# Current_sensor.net
KiCad netlist of a schematic drawn in Altium Designer
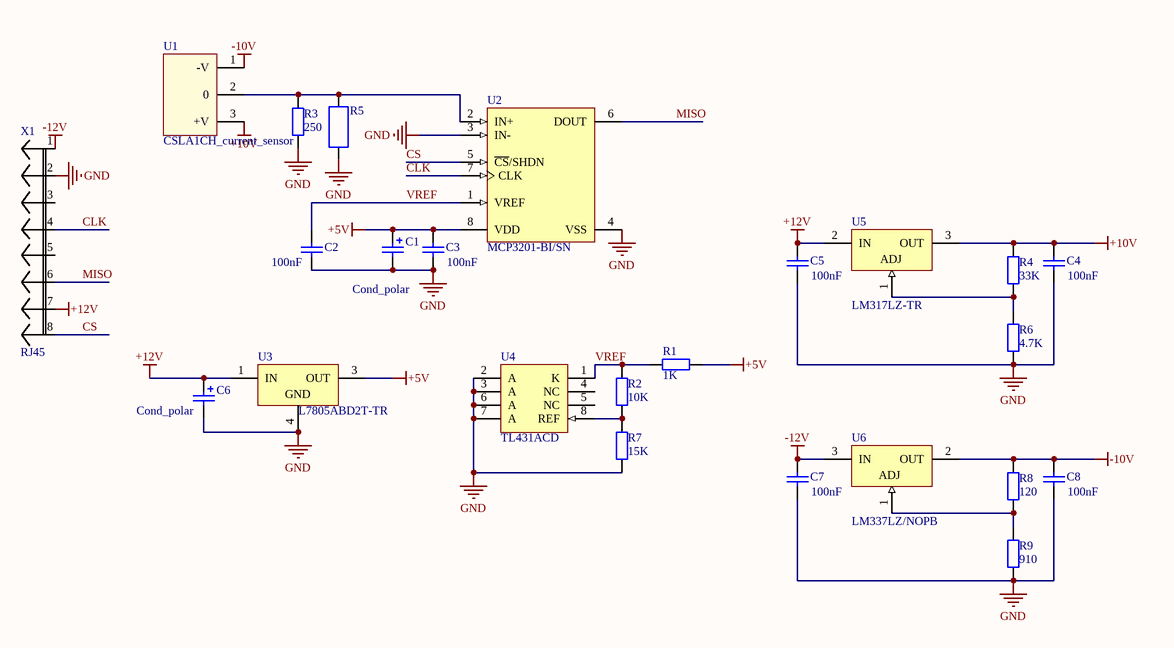
[diagram p0: Current_sensor.SchDoc]

(export (version "E")
  (design (tool "Eeschema 10.0.6"))
  (components
    (comp (ref "C1")
      (value "Cond_polar")
      (footprint "A_H_pcb_lib:CAP_EL_SMD_6.3mm")
      (libsource (lib "A_H_sch_lib") (part "Cond_polar"))
    )
    (comp (ref "C2")
      (value "100nF")
      (footprint "A_H_pcb_lib:C0805")
      (libsource (lib "A_H_sch_lib") (part "Condensator"))
    )
    (comp (ref "C3")
      (value "100nF")
      (footprint "A_H_pcb_lib:C0805")
      (libsource (lib "A_H_sch_lib") (part "Condensator"))
    )
    (comp (ref "C4")
      (value "100nF")
      (footprint "A_H_pcb_lib:C0805")
      (libsource (lib "A_H_sch_lib") (part "Condensator"))
    )
    (comp (ref "C5")
      (value "100nF")
      (footprint "A_H_pcb_lib:C0805")
      (libsource (lib "A_H_sch_lib") (part "Condensator"))
    )
    (comp (ref "C6")
      (value "Cond_polar")
      (footprint "A_H_pcb_lib:CAP_EL_SMD_6.3mm")
      (libsource (lib "A_H_sch_lib") (part "Cond_polar"))
    )
    (comp (ref "C7")
      (value "100nF")
      (footprint "A_H_pcb_lib:C0805")
      (libsource (lib "A_H_sch_lib") (part "Condensator"))
    )
    (comp (ref "C8")
      (value "100nF")
      (footprint "A_H_pcb_lib:C0805")
      (libsource (lib "A_H_sch_lib") (part "Condensator"))
    )
    (comp (ref "R1") (value "1K") (footprint "R0805") (libsource (lib "") (part "Resistor_1")))
    (comp (ref "R2") (value "10K") (footprint "R0805") (libsource (lib "A_H_sch_lib") (part "Resistor")))
    (comp (ref "R3") (value "250") (footprint "R0805") (libsource (lib "") (part "Resistor_2")))
    (comp (ref "R4") (value "33K") (footprint "R0805") (libsource (lib "") (part "Resistor_2")))
    (comp (ref "R5")
      (value "Resirtor_vivodnoi")
      (footprint "res_vivod")
      (libsource (lib "A_H_sch_lib") (part "Resirtor_vivodnoi"))
    )
    (comp (ref "R6") (value "4.7K") (footprint "R0805") (libsource (lib "") (part "Resistor_2")))
    (comp (ref "R7") (value "15K") (footprint "R0805") (libsource (lib "A_H_sch_lib") (part "Resistor")))
    (comp (ref "R8") (value "120") (footprint "R0805") (libsource (lib "") (part "Resistor_2")))
    (comp (ref "R9") (value "910") (footprint "R0805") (libsource (lib "") (part "Resistor_2")))
    (comp (ref "U1")
      (value "CSLA1CH_current_sensor")
      (footprint "A_H_pcb_lib:CSLA1CH_current_sensor")
      (libsource (lib "A_H_sch_lib") (part "CSLA1CH_current_sensor"))
    )
    (comp (ref "U2")
      (value "MCP3201-BI/SN")
      (footprint "SO8")
      (libsource (lib "A_H_sch_lib") (part "MCP3201-BI/SN"))
    )
    (comp (ref "U3")
      (value "L7805ABD2T-TR")
      (footprint "TO-263_N")
      (description "Positive Voltage Regulator, 3-Pin D2PAK, Tape and Reel")
      (libsource (lib "STMicroelectronics Power Management Linear Regulator") (part "L7805ABD2T-TR"))
    )
    (comp (ref "U4")
      (value "TL431ACD")
      (footprint "SO8_N")
      (description "Programmable Voltage Reference")
      (fields (field (name "PUBLISHER") "Altium Limited"))
      (libsource (lib "ST Power Mgt Voltage Reference") (part "TL431ACD"))
    )
    (comp (ref "U5")
      (value "LM317LZ-TR")
      (footprint "TO-92")
      (description "Low Current 1.2 to 37V Adjustable Voltage Regulator, 3-Pin TO-92, Tape and Reel")
      (libsource (lib "STMicroelectronics Power Management Linear Regulator") (part "LM317LZ-TR"))
    )
    (comp (ref "U6")
      (value "LM337LZ/NOPB")
      (footprint "Z03A")
      (description "3-Terminal Adjustable Regulator, 3-pin TO-92, Pb-Free")
      (fields (field (name "MANUFACTURER") "National Semiconductor"))
      (libsource (lib "National Semiconductor LDO") (part "LM337LZ/NOPB"))
    )
    (comp (ref "X1")
      (value "RJ45")
      (footprint "A_H_pcb_lib:RJ45")
      (libsource (lib "A_H_sch_lib") (part "RJ45"))
    )
  )
  (nets
    (net (code "1") (name "+5V") (class "Default")
      (node (ref "C1") (pin "1") (pinfunction "1_1") (pintype "passive"))
      (node (ref "C3") (pin "2") (pinfunction "2_2") (pintype "passive"))
      (node (ref "R1") (pin "1") (pinfunction "1_1") (pintype "passive"))
      (node (ref "U2") (pin "8") (pinfunction "VDD_8") (pintype "power_in"))
      (node (ref "U3") (pin "3") (pinfunction "OUT_3") (pintype "power_in"))
    )
    (net (code "2") (name "+10V") (class "Default")
      (node (ref "C4") (pin "2") (pinfunction "2_2") (pintype "passive"))
      (node (ref "R4") (pin "1") (pinfunction "1_1") (pintype "passive"))
      (node (ref "U1") (pin "3") (pinfunction "+V_3") (pintype "passive"))
      (node (ref "U5") (pin "3") (pinfunction "OUT_3") (pintype "power_in"))
    )
    (net (code "3") (name "+12V") (class "Default")
      (node (ref "C5") (pin "2") (pinfunction "2_2") (pintype "passive"))
      (node (ref "C6") (pin "1") (pinfunction "1_1") (pintype "passive"))
      (node (ref "U3") (pin "1") (pinfunction "IN_1") (pintype "power_in"))
      (node (ref "U5") (pin "2") (pinfunction "IN_2") (pintype "power_in"))
      (node (ref "X1") (pin "7") (pinfunction "7_7") (pintype "passive"))
    )
    (net (code "4") (name "-10V") (class "Default")
      (node (ref "C8") (pin "2") (pinfunction "2_2") (pintype "passive"))
      (node (ref "R8") (pin "1") (pinfunction "1_1") (pintype "passive"))
      (node (ref "U1") (pin "1") (pinfunction "-V_1") (pintype "passive"))
      (node (ref "U6") (pin "2") (pinfunction "OUT_2") (pintype "power_in"))
    )
    (net (code "5") (name "-12V") (class "Default")
      (node (ref "C7") (pin "2") (pinfunction "2_2") (pintype "passive"))
      (node (ref "U6") (pin "3") (pinfunction "IN_3") (pintype "power_in"))
      (node (ref "X1") (pin "1") (pinfunction "1_1") (pintype "passive"))
    )
    (net (code "6") (name "/CLK") (class "Default")
      (node (ref "U2") (pin "7") (pinfunction "CLK_7") (pintype "input"))
      (node (ref "X1") (pin "4") (pinfunction "4_4") (pintype "passive"))
    )
    (net (code "7") (name "/CS") (class "Default")
      (node (ref "U2") (pin "5") (pinfunction "~{CS}/SHDN_5") (pintype "input"))
      (node (ref "X1") (pin "8") (pinfunction "8_8") (pintype "passive"))
    )
    (net (code "8") (name "/MISO") (class "Default")
      (node (ref "U2") (pin "6") (pinfunction "DOUT_6") (pintype "tri_state"))
      (node (ref "X1") (pin "6") (pinfunction "6_6") (pintype "passive"))
    )
    (net (code "9") (name "/VREF") (class "Default")
      (node (ref "C2") (pin "2") (pinfunction "2_2") (pintype "passive"))
      (node (ref "R1") (pin "2") (pinfunction "2_2") (pintype "passive"))
      (node (ref "R2") (pin "2") (pinfunction "2_2") (pintype "passive"))
      (node (ref "U2") (pin "1") (pinfunction "VREF_1") (pintype "input"))
      (node (ref "U4") (pin "1") (pinfunction "K_1") (pintype "passive"))
    )
    (net (code "10") (name "GND") (class "Default")
      (node (ref "C1") (pin "2") (pinfunction "2_2") (pintype "passive"))
      (node (ref "C2") (pin "1") (pinfunction "1_1") (pintype "passive"))
      (node (ref "C3") (pin "1") (pinfunction "1_1") (pintype "passive"))
      (node (ref "C4") (pin "1") (pinfunction "1_1") (pintype "passive"))
      (node (ref "C5") (pin "1") (pinfunction "1_1") (pintype "passive"))
      (node (ref "C6") (pin "2") (pinfunction "2_2") (pintype "passive"))
      (node (ref "C7") (pin "1") (pinfunction "1_1") (pintype "passive"))
      (node (ref "C8") (pin "1") (pinfunction "1_1") (pintype "passive"))
      (node (ref "R3") (pin "2") (pinfunction "2_2") (pintype "passive"))
      (node (ref "R5") (pin "1") (pinfunction "3_1") (pintype "passive"))
      (node (ref "R6") (pin "2") (pinfunction "2_2") (pintype "passive"))
      (node (ref "R7") (pin "1") (pinfunction "1_1") (pintype "passive"))
      (node (ref "R9") (pin "2") (pinfunction "2_2") (pintype "passive"))
      (node (ref "U2") (pin "3") (pinfunction "IN-_3") (pintype "input"))
      (node (ref "U2") (pin "4") (pinfunction "VSS_4") (pintype "power_in"))
      (node (ref "U3") (pin "4") (pinfunction "GND_4") (pintype "power_in"))
      (node (ref "U4") (pin "2") (pinfunction "A_2") (pintype "passive"))
      (node (ref "U4") (pin "3") (pinfunction "A_3") (pintype "passive"))
      (node (ref "U4") (pin "6") (pinfunction "A_6") (pintype "passive"))
      (node (ref "U4") (pin "7") (pinfunction "A_7") (pintype "passive"))
      (node (ref "X1") (pin "2") (pinfunction "2_2") (pintype "passive"))
    )
    (net (code "11") (name "Net-(R5-4)") (class "Default")
      (node (ref "R3") (pin "1") (pinfunction "1_1") (pintype "passive"))
      (node (ref "R5") (pin "2") (pinfunction "4_2") (pintype "passive"))
      (node (ref "U1") (pin "2") (pinfunction "0_2") (pintype "passive"))
      (node (ref "U2") (pin "2") (pinfunction "IN+_2") (pintype "input"))
    )
    (net (code "12") (name "Net-(U4-REF)") (class "Default")
      (node (ref "R2") (pin "1") (pinfunction "1_1") (pintype "passive"))
      (node (ref "R7") (pin "2") (pinfunction "2_2") (pintype "passive"))
      (node (ref "U4") (pin "8") (pinfunction "REF_8") (pintype "input"))
    )
    (net (code "13") (name "Net-(U5-ADJ)") (class "Default")
      (node (ref "R4") (pin "2") (pinfunction "2_2") (pintype "passive"))
      (node (ref "R6") (pin "1") (pinfunction "1_1") (pintype "passive"))
      (node (ref "U5") (pin "1") (pinfunction "ADJ_1") (pintype "input"))
    )
    (net (code "14") (name "Net-(U6-ADJ)") (class "Default")
      (node (ref "R8") (pin "2") (pinfunction "2_2") (pintype "passive"))
      (node (ref "R9") (pin "1") (pinfunction "1_1") (pintype "passive"))
      (node (ref "U6") (pin "1") (pinfunction "ADJ_1") (pintype "input"))
    )
    (net (code "15") (name "unconnected-(U4-NC-Pad4)") (class "Default")
      (node (ref "U4") (pin "4") (pinfunction "NC_4") (pintype "passive"))
    )
    (net (code "16") (name "unconnected-(U4-NC-Pad5)") (class "Default")
      (node (ref "U4") (pin "5") (pinfunction "NC_5") (pintype "passive"))
    )
    (net (code "17") (name "unconnected-(X1-Pad3)") (class "Default")
      (node (ref "X1") (pin "3") (pinfunction "3_3") (pintype "passive"))
    )
    (net (code "18") (name "unconnected-(X1-Pad5)") (class "Default")
      (node (ref "X1") (pin "5") (pinfunction "5_5") (pintype "passive"))
    )
  )
)
